# MxxxSMT.net
KiCad netlist of a schematic drawn in EAGLE
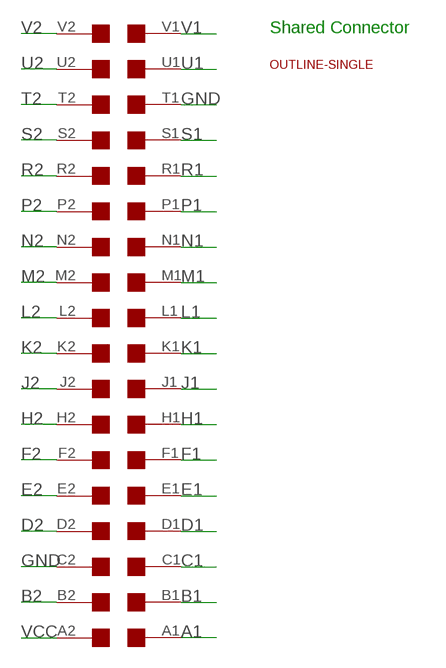
[diagram p0: schematic, sheet 1]
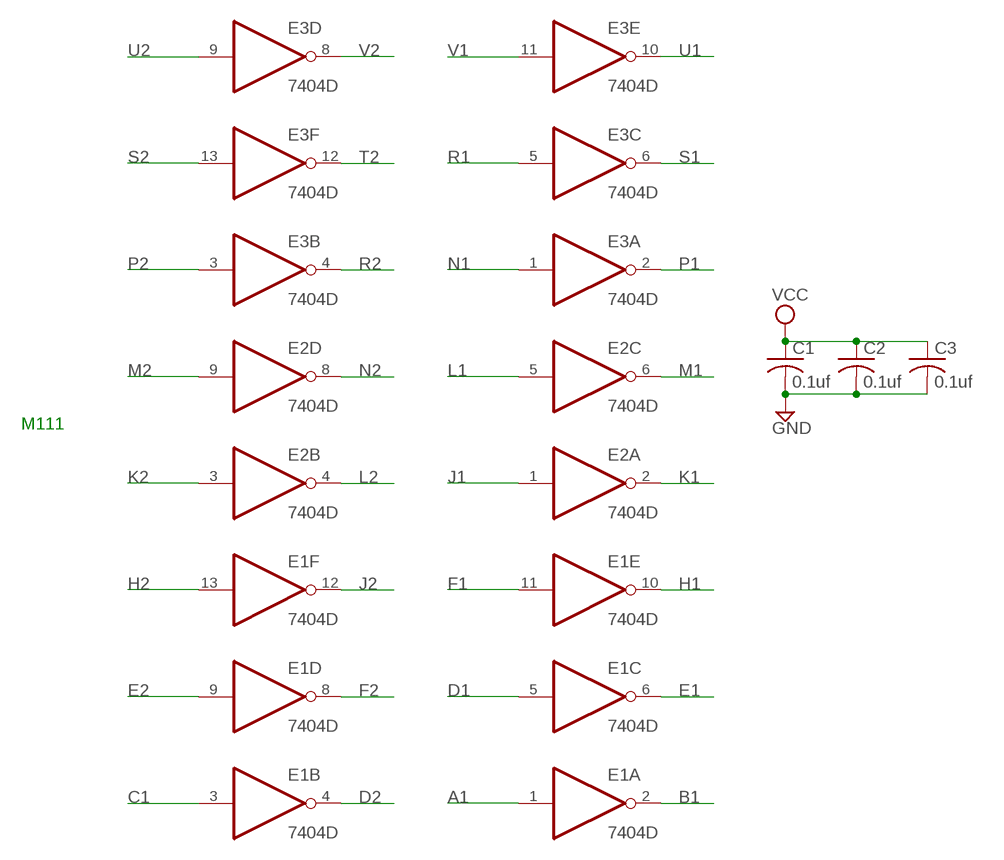
[diagram p1: schematic, sheet 2]
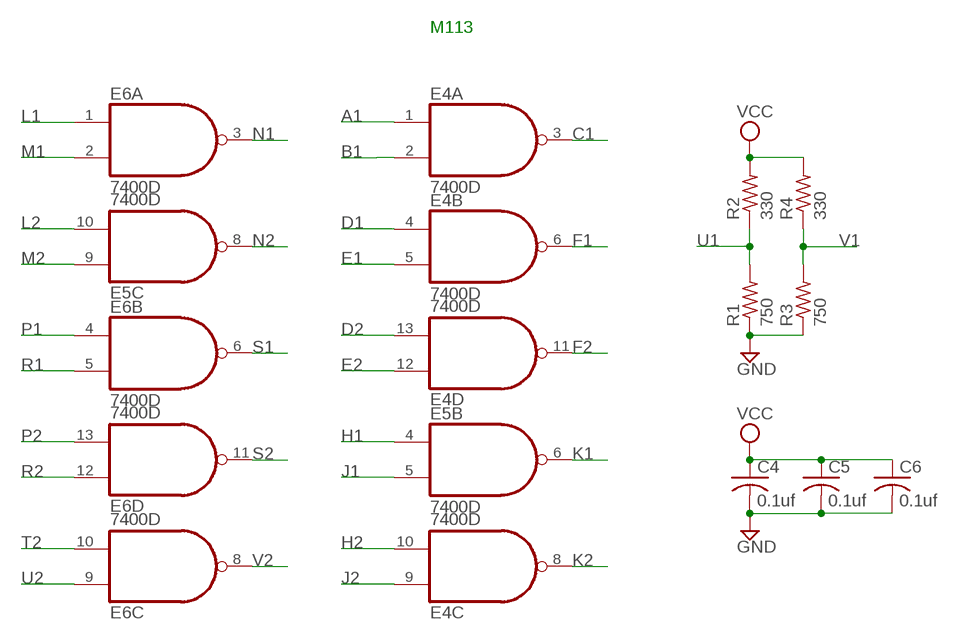
[diagram p2: schematic, sheet 3]
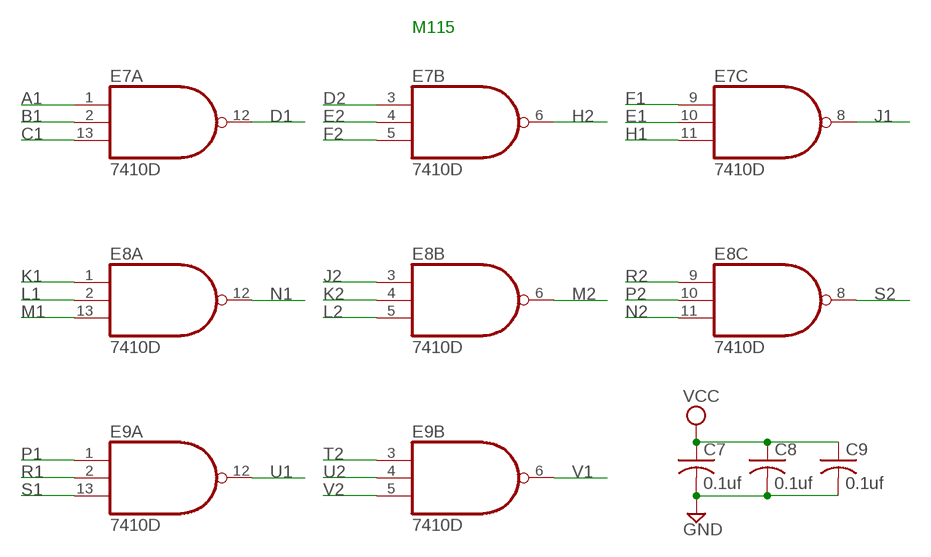
[diagram p3: schematic, sheet 4]
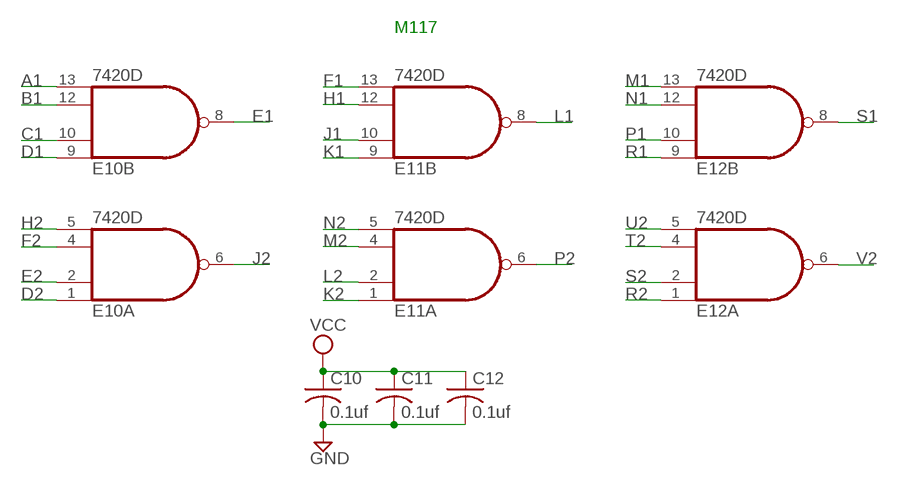
[diagram p4: schematic, sheet 5]
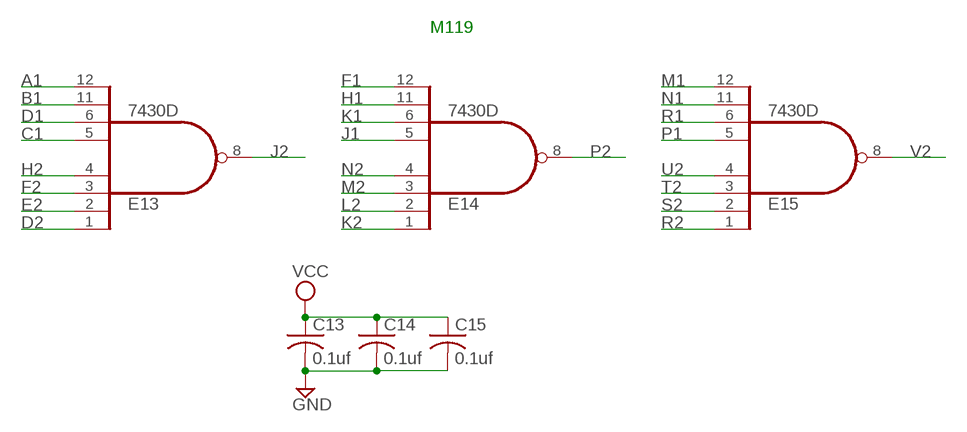
[diagram p5: schematic, sheet 6]
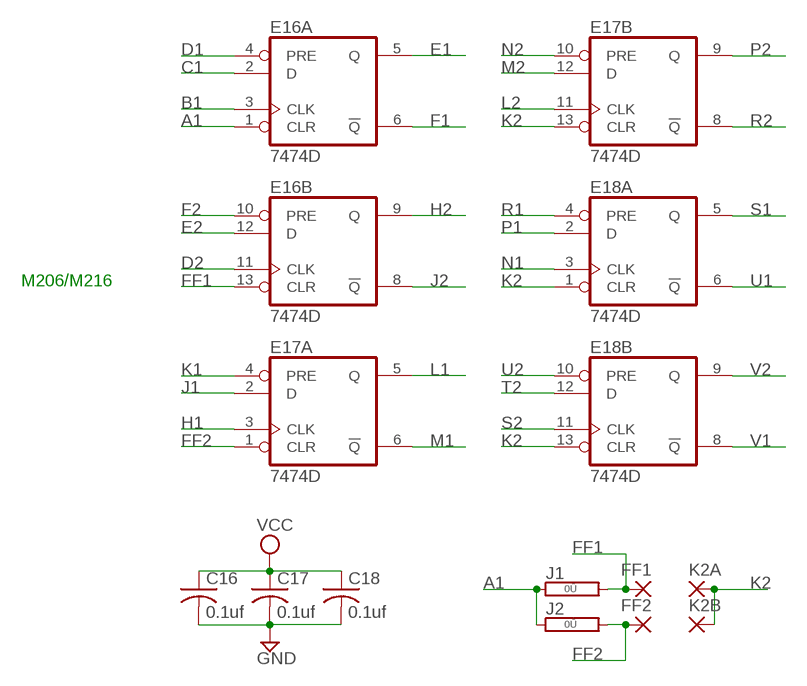
[diagram p6: schematic, sheet 7]
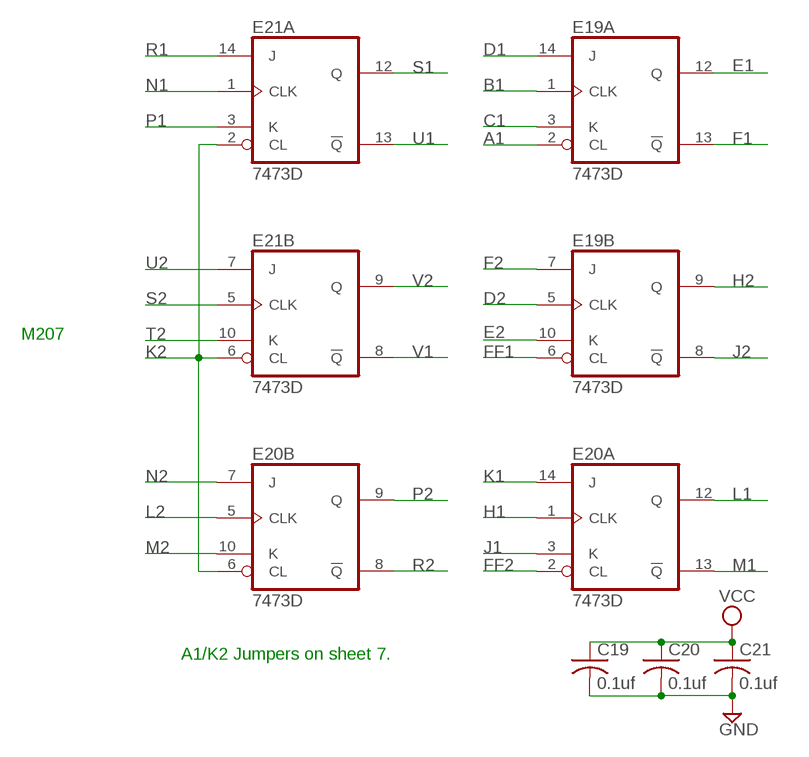
[diagram p7: schematic, sheet 8]

(export (version "E")
  (design (tool "Eeschema 10.0.6"))
  (components
    (comp (ref "C4")
      (value "0.1uf")
      (footprint "eagle-import:C050-025X075")
      (libsource (lib "eagle-import") (part "C-US050-025X075"))
    )
    (comp (ref "C5")
      (value "0.1uf")
      (footprint "eagle-import:C050-025X075")
      (libsource (lib "eagle-import") (part "C-US050-025X075"))
    )
    (comp (ref "C6")
      (value "0.1uf")
      (footprint "eagle-import:C050-025X075")
      (libsource (lib "eagle-import") (part "C-US050-025X075"))
    )
    (comp (ref "E4")
      (value "7400D")
      (footprint "eagle-import:SO14")
      (libsource (lib "eagle-import") (part "7400D"))
    )
    (comp (ref "E5")
      (value "7400D")
      (footprint "eagle-import:SO14")
      (libsource (lib "eagle-import") (part "7400D"))
    )
    (comp (ref "E6")
      (value "7400D")
      (footprint "eagle-import:SO14")
      (libsource (lib "eagle-import") (part "7400D"))
    )
    (comp (ref "R1")
      (value "750")
      (footprint "eagle-import:0207_10")
      (libsource (lib "eagle-import") (part "R-US_0207/10"))
    )
    (comp (ref "R2")
      (value "330")
      (footprint "eagle-import:0207_10")
      (libsource (lib "eagle-import") (part "R-US_0207/10"))
    )
    (comp (ref "R3")
      (value "750")
      (footprint "eagle-import:0207_10")
      (libsource (lib "eagle-import") (part "R-US_0207/10"))
    )
    (comp (ref "R4")
      (value "330")
      (footprint "eagle-import:0207_10")
      (libsource (lib "eagle-import") (part "R-US_0207/10"))
    )
    (comp (ref "C16")
      (value "0.1uf")
      (footprint "eagle-import:C050-025X075")
      (libsource (lib "eagle-import") (part "C-US050-025X075"))
    )
    (comp (ref "C17")
      (value "0.1uf")
      (footprint "eagle-import:C050-025X075")
      (libsource (lib "eagle-import") (part "C-US050-025X075"))
    )
    (comp (ref "C18")
      (value "0.1uf")
      (footprint "eagle-import:C050-025X075")
      (libsource (lib "eagle-import") (part "C-US050-025X075"))
    )
    (comp (ref "E16")
      (value "7474D")
      (footprint "eagle-import:SO14")
      (libsource (lib "eagle-import") (part "7474DS"))
    )
    (comp (ref "E17")
      (value "7474D")
      (footprint "eagle-import:SO14")
      (libsource (lib "eagle-import") (part "7474DS"))
    )
    (comp (ref "E18")
      (value "7474D")
      (footprint "eagle-import:SO14")
      (libsource (lib "eagle-import") (part "7474DS"))
    )
    (comp (ref "FF1")
      (value "1,6/0,8")
      (footprint "eagle-import:1,6_0,8")
      (libsource (lib "eagle-import") (part "1,6/0,8"))
    )
    (comp (ref "FF2")
      (value "1,6/0,8")
      (footprint "eagle-import:1,6_0,8")
      (libsource (lib "eagle-import") (part "1,6/0,8"))
    )
    (comp (ref "J1")
      (value "0R")
      (footprint "eagle-import:0R_10")
      (libsource (lib "eagle-import") (part "0R"))
    )
    (comp (ref "J2")
      (value "0R")
      (footprint "eagle-import:0R_10")
      (libsource (lib "eagle-import") (part "0R"))
    )
    (comp (ref "K2A")
      (value "1,6/0,8")
      (footprint "eagle-import:1,6_0,8")
      (libsource (lib "eagle-import") (part "1,6/0,8"))
    )
    (comp (ref "K2B")
      (value "1,6/0,8")
      (footprint "eagle-import:1,6_0,8")
      (libsource (lib "eagle-import") (part "1,6/0,8"))
    )
    (comp (ref "C13")
      (value "0.1uf")
      (footprint "eagle-import:C050-025X075")
      (libsource (lib "eagle-import") (part "C-US050-025X075"))
    )
    (comp (ref "C14")
      (value "0.1uf")
      (footprint "eagle-import:C050-025X075")
      (libsource (lib "eagle-import") (part "C-US050-025X075"))
    )
    (comp (ref "C15")
      (value "0.1uf")
      (footprint "eagle-import:C050-025X075")
      (libsource (lib "eagle-import") (part "C-US050-025X075"))
    )
    (comp (ref "E13")
      (value "7430D")
      (footprint "eagle-import:SO14")
      (libsource (lib "eagle-import") (part "7430D"))
    )
    (comp (ref "E14")
      (value "7430D")
      (footprint "eagle-import:SO14")
      (libsource (lib "eagle-import") (part "7430D"))
    )
    (comp (ref "E15")
      (value "7430D")
      (footprint "eagle-import:SO14")
      (libsource (lib "eagle-import") (part "7430D"))
    )
    (comp (ref "C19")
      (value "0.1uf")
      (footprint "eagle-import:C050-025X075")
      (libsource (lib "eagle-import") (part "C-US050-025X075"))
    )
    (comp (ref "C20")
      (value "0.1uf")
      (footprint "eagle-import:C050-025X075")
      (libsource (lib "eagle-import") (part "C-US050-025X075"))
    )
    (comp (ref "C21")
      (value "0.1uf")
      (footprint "eagle-import:C050-025X075")
      (libsource (lib "eagle-import") (part "C-US050-025X075"))
    )
    (comp (ref "E19")
      (value "7473D")
      (footprint "eagle-import:SO14")
      (libsource (lib "eagle-import") (part "7473DLS"))
    )
    (comp (ref "E20")
      (value "7473D")
      (footprint "eagle-import:SO14")
      (libsource (lib "eagle-import") (part "7473DLS"))
    )
    (comp (ref "E21")
      (value "7473D")
      (footprint "eagle-import:SO14")
      (libsource (lib "eagle-import") (part "7473DLS"))
    )
    (comp (ref "C7")
      (value "0.1uf")
      (footprint "eagle-import:C050-025X075")
      (libsource (lib "eagle-import") (part "C-US050-025X075"))
    )
    (comp (ref "C8")
      (value "0.1uf")
      (footprint "eagle-import:C050-025X075")
      (libsource (lib "eagle-import") (part "C-US050-025X075"))
    )
    (comp (ref "C9")
      (value "0.1uf")
      (footprint "eagle-import:C050-025X075")
      (libsource (lib "eagle-import") (part "C-US050-025X075"))
    )
    (comp (ref "E7")
      (value "7410D")
      (footprint "eagle-import:SO14")
      (libsource (lib "eagle-import") (part "7410D"))
    )
    (comp (ref "E8")
      (value "7410D")
      (footprint "eagle-import:SO14")
      (libsource (lib "eagle-import") (part "7410D"))
    )
    (comp (ref "E9")
      (value "7410D")
      (footprint "eagle-import:SO14")
      (libsource (lib "eagle-import") (part "7410D"))
    )
    (comp (ref "C1")
      (value "0.1uf")
      (footprint "eagle-import:C050-025X075")
      (libsource (lib "eagle-import") (part "C-US050-025X075"))
    )
    (comp (ref "C2")
      (value "0.1uf")
      (footprint "eagle-import:C050-025X075")
      (libsource (lib "eagle-import") (part "C-US050-025X075"))
    )
    (comp (ref "C3")
      (value "0.1uf")
      (footprint "eagle-import:C050-025X075")
      (libsource (lib "eagle-import") (part "C-US050-025X075"))
    )
    (comp (ref "E1")
      (value "7404D")
      (footprint "eagle-import:SO14")
      (libsource (lib "eagle-import") (part "7404D"))
    )
    (comp (ref "E2")
      (value "7404D")
      (footprint "eagle-import:SO14")
      (libsource (lib "eagle-import") (part "7404D"))
    )
    (comp (ref "E3")
      (value "7404D")
      (footprint "eagle-import:SO14")
      (libsource (lib "eagle-import") (part "7404D"))
    )
    (comp (ref "C10")
      (value "0.1uf")
      (footprint "eagle-import:C050-025X075")
      (libsource (lib "eagle-import") (part "C-US050-025X075"))
    )
    (comp (ref "C11")
      (value "0.1uf")
      (footprint "eagle-import:C050-025X075")
      (libsource (lib "eagle-import") (part "C-US050-025X075"))
    )
    (comp (ref "C12")
      (value "0.1uf")
      (footprint "eagle-import:C050-025X075")
      (libsource (lib "eagle-import") (part "C-US050-025X075"))
    )
    (comp (ref "E10")
      (value "7420D")
      (footprint "eagle-import:SO14")
      (libsource (lib "eagle-import") (part "7420DS"))
    )
    (comp (ref "E11")
      (value "7420D")
      (footprint "eagle-import:SO14")
      (libsource (lib "eagle-import") (part "7420DS"))
    )
    (comp (ref "E12")
      (value "7420D")
      (footprint "eagle-import:SO14")
      (libsource (lib "eagle-import") (part "7420DS"))
    )
    (comp (ref "U$1")
      (value "EDGE-2CONNECTOR")
      (footprint "eagle-import:EDGE-CON2")
      (libsource (lib "eagle-import") (part "EDGE-2CONNECTOR"))
    )
    (comp (ref "U$4")
      (value "OUTLINE-SINGLE")
      (footprint "eagle-import:SINGLE")
      (libsource (lib "eagle-import") (part "OUTLINE-SINGLE"))
    )
  )
  (nets
    (net (code "1") (name "A1") (class "Default")
      (node (ref "E1") (pin "1") (pinfunction "I_1") (pintype "input"))
      (node (ref "E10") (pin "13") (pinfunction "I3_13") (pintype "input"))
      (node (ref "E13") (pin "12") (pinfunction "I7_12") (pintype "input"))
      (node (ref "E16") (pin "1") (pinfunction "CLR_1") (pintype "input"))
      (node (ref "E19") (pin "2") (pinfunction "CL_2") (pintype "input"))
      (node (ref "E4") (pin "1") (pinfunction "I0_1") (pintype "input"))
      (node (ref "E7") (pin "1") (pinfunction "I0_1") (pintype "input"))
      (node (ref "J1") (pin "1") (pinfunction "1_1") (pintype "passive"))
      (node (ref "J2") (pin "1") (pinfunction "1_1") (pintype "passive"))
      (node (ref "U$1") (pin "A1") (pinfunction "1_A1") (pintype "bidirectional"))
    )
    (net (code "2") (name "B1") (class "Default")
      (node (ref "E1") (pin "2") (pinfunction "O_2") (pintype "output"))
      (node (ref "E10") (pin "12") (pinfunction "I2_12") (pintype "input"))
      (node (ref "E13") (pin "11") (pinfunction "I6_11") (pintype "input"))
      (node (ref "E16") (pin "3") (pinfunction "CLK_3") (pintype "input"))
      (node (ref "E19") (pin "1") (pinfunction "CLK_1") (pintype "input"))
      (node (ref "E4") (pin "2") (pinfunction "I1_2") (pintype "input"))
      (node (ref "E7") (pin "2") (pinfunction "I1_2") (pintype "input"))
      (node (ref "U$1") (pin "B1") (pinfunction "1_B1") (pintype "bidirectional"))
    )
    (net (code "3") (name "B2") (class "Default")
      (node (ref "U$1") (pin "B2") (pinfunction "1_B2") (pintype "bidirectional"))
    )
    (net (code "4") (name "C1") (class "Default")
      (node (ref "E1") (pin "3") (pinfunction "I_3") (pintype "input"))
      (node (ref "E10") (pin "10") (pinfunction "I1_10") (pintype "input"))
      (node (ref "E13") (pin "5") (pinfunction "I4_5") (pintype "input"))
      (node (ref "E16") (pin "2") (pinfunction "D_2") (pintype "input"))
      (node (ref "E19") (pin "3") (pinfunction "K_3") (pintype "input"))
      (node (ref "E4") (pin "3") (pinfunction "O_3") (pintype "output"))
      (node (ref "E7") (pin "13") (pinfunction "I2_13") (pintype "input"))
      (node (ref "U$1") (pin "C1") (pinfunction "1_C1") (pintype "bidirectional"))
    )
    (net (code "5") (name "D1") (class "Default")
      (node (ref "E1") (pin "5") (pinfunction "I_5") (pintype "input"))
      (node (ref "E10") (pin "9") (pinfunction "I0_9") (pintype "input"))
      (node (ref "E13") (pin "6") (pinfunction "I5_6") (pintype "input"))
      (node (ref "E16") (pin "4") (pinfunction "PRE_4") (pintype "input"))
      (node (ref "E19") (pin "14") (pinfunction "J_14") (pintype "input"))
      (node (ref "E4") (pin "4") (pinfunction "I0_4") (pintype "input"))
      (node (ref "E7") (pin "12") (pinfunction "O_12") (pintype "output"))
      (node (ref "U$1") (pin "D1") (pinfunction "1_D1") (pintype "bidirectional"))
    )
    (net (code "6") (name "D2") (class "Default")
      (node (ref "E1") (pin "4") (pinfunction "O_4") (pintype "output"))
      (node (ref "E10") (pin "1") (pinfunction "I0_1") (pintype "input"))
      (node (ref "E13") (pin "1") (pinfunction "I0_1") (pintype "input"))
      (node (ref "E16") (pin "11") (pinfunction "CLK_11") (pintype "input"))
      (node (ref "E19") (pin "5") (pinfunction "CLK_5") (pintype "input"))
      (node (ref "E4") (pin "13") (pinfunction "I1_13") (pintype "input"))
      (node (ref "E7") (pin "3") (pinfunction "I0_3") (pintype "input"))
      (node (ref "U$1") (pin "D2") (pinfunction "1_D2") (pintype "bidirectional"))
    )
    (net (code "7") (name "E1") (class "Default")
      (node (ref "E1") (pin "6") (pinfunction "O_6") (pintype "output"))
      (node (ref "E10") (pin "8") (pinfunction "O_8") (pintype "output"))
      (node (ref "E16") (pin "5") (pinfunction "Q_5") (pintype "output"))
      (node (ref "E19") (pin "12") (pinfunction "Q_12") (pintype "output"))
      (node (ref "E4") (pin "5") (pinfunction "I1_5") (pintype "input"))
      (node (ref "E7") (pin "10") (pinfunction "I1_10") (pintype "input"))
      (node (ref "U$1") (pin "E1") (pinfunction "1_E1") (pintype "bidirectional"))
    )
    (net (code "8") (name "E2") (class "Default")
      (node (ref "E1") (pin "9") (pinfunction "I_9") (pintype "input"))
      (node (ref "E10") (pin "2") (pinfunction "I1_2") (pintype "input"))
      (node (ref "E13") (pin "2") (pinfunction "I1_2") (pintype "input"))
      (node (ref "E16") (pin "12") (pinfunction "D_12") (pintype "input"))
      (node (ref "E19") (pin "10") (pinfunction "K_10") (pintype "input"))
      (node (ref "E4") (pin "12") (pinfunction "I0_12") (pintype "input"))
      (node (ref "E7") (pin "4") (pinfunction "I1_4") (pintype "input"))
      (node (ref "U$1") (pin "E2") (pinfunction "1_E2") (pintype "bidirectional"))
    )
    (net (code "9") (name "F1") (class "Default")
      (node (ref "E1") (pin "11") (pinfunction "I_11") (pintype "input"))
      (node (ref "E11") (pin "13") (pinfunction "I3_13") (pintype "input"))
      (node (ref "E14") (pin "12") (pinfunction "I7_12") (pintype "input"))
      (node (ref "E16") (pin "6") (pinfunction "~{Q}_6") (pintype "output"))
      (node (ref "E19") (pin "13") (pinfunction "~{Q}_13") (pintype "output"))
      (node (ref "E4") (pin "6") (pinfunction "O_6") (pintype "output"))
      (node (ref "E7") (pin "9") (pinfunction "I0_9") (pintype "input"))
      (node (ref "U$1") (pin "F1") (pinfunction "1_F1") (pintype "bidirectional"))
    )
    (net (code "10") (name "F2") (class "Default")
      (node (ref "E1") (pin "8") (pinfunction "O_8") (pintype "output"))
      (node (ref "E10") (pin "4") (pinfunction "I2_4") (pintype "input"))
      (node (ref "E13") (pin "3") (pinfunction "I2_3") (pintype "input"))
      (node (ref "E16") (pin "10") (pinfunction "PRE_10") (pintype "input"))
      (node (ref "E19") (pin "7") (pinfunction "J_7") (pintype "input"))
      (node (ref "E4") (pin "11") (pinfunction "O_11") (pintype "output"))
      (node (ref "E7") (pin "5") (pinfunction "I2_5") (pintype "input"))
      (node (ref "U$1") (pin "F2") (pinfunction "1_F2") (pintype "bidirectional"))
    )
    (net (code "11") (name "FF1") (class "Default")
      (node (ref "E16") (pin "13") (pinfunction "CLR_13") (pintype "input"))
      (node (ref "E19") (pin "6") (pinfunction "CL_6") (pintype "input"))
      (node (ref "FF1") (pin "1") (pinfunction "P_1") (pintype "passive"))
      (node (ref "J1") (pin "2") (pinfunction "2_2") (pintype "passive"))
    )
    (net (code "12") (name "FF2") (class "Default")
      (node (ref "E17") (pin "1") (pinfunction "CLR_1") (pintype "input"))
      (node (ref "E20") (pin "2") (pinfunction "CL_2") (pintype "input"))
      (node (ref "FF2") (pin "1") (pinfunction "P_1") (pintype "passive"))
      (node (ref "J2") (pin "2") (pinfunction "2_2") (pintype "passive"))
    )
    (net (code "13") (name "GND") (class "Default")
      (node (ref "C1") (pin "2") (pinfunction "2_2") (pintype "passive"))
      (node (ref "C10") (pin "2") (pinfunction "2_2") (pintype "passive"))
      (node (ref "C11") (pin "2") (pinfunction "2_2") (pintype "passive"))
      (node (ref "C12") (pin "2") (pinfunction "2_2") (pintype "passive"))
      (node (ref "C13") (pin "2") (pinfunction "2_2") (pintype "passive"))
      (node (ref "C14") (pin "2") (pinfunction "2_2") (pintype "passive"))
      (node (ref "C15") (pin "2") (pinfunction "2_2") (pintype "passive"))
      (node (ref "C16") (pin "2") (pinfunction "2_2") (pintype "passive"))
      (node (ref "C17") (pin "2") (pinfunction "2_2") (pintype "passive"))
      (node (ref "C18") (pin "2") (pinfunction "2_2") (pintype "passive"))
      (node (ref "C19") (pin "2") (pinfunction "2_2") (pintype "passive"))
      (node (ref "C2") (pin "2") (pinfunction "2_2") (pintype "passive"))
      (node (ref "C20") (pin "2") (pinfunction "2_2") (pintype "passive"))
      (node (ref "C21") (pin "2") (pinfunction "2_2") (pintype "passive"))
      (node (ref "C3") (pin "2") (pinfunction "2_2") (pintype "passive"))
      (node (ref "C4") (pin "2") (pinfunction "2_2") (pintype "passive"))
      (node (ref "C5") (pin "2") (pinfunction "2_2") (pintype "passive"))
      (node (ref "C6") (pin "2") (pinfunction "2_2") (pintype "passive"))
      (node (ref "C7") (pin "2") (pinfunction "2_2") (pintype "passive"))
      (node (ref "C8") (pin "2") (pinfunction "2_2") (pintype "passive"))
      (node (ref "C9") (pin "2") (pinfunction "2_2") (pintype "passive"))
      (node (ref "R1") (pin "1") (pinfunction "1_1") (pintype "passive"))
      (node (ref "R3") (pin "1") (pinfunction "1_1") (pintype "passive"))
      (node (ref "U$1") (pin "C2") (pinfunction "1_C2") (pintype "bidirectional"))
      (node (ref "U$1") (pin "T1") (pinfunction "1_T1") (pintype "bidirectional"))
    )
    (net (code "14") (name "H1") (class "Default")
      (node (ref "E1") (pin "10") (pinfunction "O_10") (pintype "output"))
      (node (ref "E11") (pin "12") (pinfunction "I2_12") (pintype "input"))
      (node (ref "E14") (pin "11") (pinfunction "I6_11") (pintype "input"))
      (node (ref "E17") (pin "3") (pinfunction "CLK_3") (pintype "input"))
      (node (ref "E20") (pin "1") (pinfunction "CLK_1") (pintype "input"))
      (node (ref "E5") (pin "4") (pinfunction "I0_4") (pintype "input"))
      (node (ref "E7") (pin "11") (pinfunction "I2_11") (pintype "input"))
      (node (ref "U$1") (pin "H1") (pinfunction "1_H1") (pintype "bidirectional"))
    )
    (net (code "15") (name "H2") (class "Default")
      (node (ref "E1") (pin "13") (pinfunction "I_13") (pintype "input"))
      (node (ref "E10") (pin "5") (pinfunction "I3_5") (pintype "input"))
      (node (ref "E13") (pin "4") (pinfunction "I3_4") (pintype "input"))
      (node (ref "E16") (pin "9") (pinfunction "Q_9") (pintype "output"))
      (node (ref "E19") (pin "9") (pinfunction "Q_9") (pintype "output"))
      (node (ref "E4") (pin "10") (pinfunction "I1_10") (pintype "input"))
      (node (ref "E7") (pin "6") (pinfunction "O_6") (pintype "output"))
      (node (ref "U$1") (pin "H2") (pinfunction "1_H2") (pintype "bidirectional"))
    )
    (net (code "16") (name "J1") (class "Default")
      (node (ref "E11") (pin "10") (pinfunction "I1_10") (pintype "input"))
      (node (ref "E14") (pin "5") (pinfunction "I4_5") (pintype "input"))
      (node (ref "E17") (pin "2") (pinfunction "D_2") (pintype "input"))
      (node (ref "E2") (pin "1") (pinfunction "I_1") (pintype "input"))
      (node (ref "E20") (pin "3") (pinfunction "K_3") (pintype "input"))
      (node (ref "E5") (pin "5") (pinfunction "I1_5") (pintype "input"))
      (node (ref "E7") (pin "8") (pinfunction "O_8") (pintype "output"))
      (node (ref "U$1") (pin "J1") (pinfunction "1_J1") (pintype "bidirectional"))
    )
    (net (code "17") (name "J2") (class "Default")
      (node (ref "E1") (pin "12") (pinfunction "O_12") (pintype "output"))
      (node (ref "E10") (pin "6") (pinfunction "O_6") (pintype "output"))
      (node (ref "E13") (pin "8") (pinfunction "O_8") (pintype "output"))
      (node (ref "E16") (pin "8") (pinfunction "~{Q}_8") (pintype "output"))
      (node (ref "E19") (pin "8") (pinfunction "~{Q}_8") (pintype "output"))
      (node (ref "E4") (pin "9") (pinfunction "I0_9") (pintype "input"))
      (node (ref "E8") (pin "3") (pinfunction "I0_3") (pintype "input"))
      (node (ref "U$1") (pin "J2") (pinfunction "1_J2") (pintype "bidirectional"))
    )
    (net (code "18") (name "K1") (class "Default")
      (node (ref "E11") (pin "9") (pinfunction "I0_9") (pintype "input"))
      (node (ref "E14") (pin "6") (pinfunction "I5_6") (pintype "input"))
      (node (ref "E17") (pin "4") (pinfunction "PRE_4") (pintype "input"))
      (node (ref "E2") (pin "2") (pinfunction "O_2") (pintype "output"))
      (node (ref "E20") (pin "14") (pinfunction "J_14") (pintype "input"))
      (node (ref "E5") (pin "6") (pinfunction "O_6") (pintype "output"))
      (node (ref "E8") (pin "1") (pinfunction "I0_1") (pintype "input"))
      (node (ref "U$1") (pin "K1") (pinfunction "1_K1") (pintype "bidirectional"))
    )
    (net (code "19") (name "K2") (class "Default")
      (node (ref "E11") (pin "1") (pinfunction "I0_1") (pintype "input"))
      (node (ref "E14") (pin "1") (pinfunction "I0_1") (pintype "input"))
      (node (ref "E17") (pin "13") (pinfunction "CLR_13") (pintype "input"))
      (node (ref "E18") (pin "1") (pinfunction "CLR_1") (pintype "input"))
      (node (ref "E18") (pin "13") (pinfunction "CLR_13") (pintype "input"))
      (node (ref "E2") (pin "3") (pinfunction "I_3") (pintype "input"))
      (node (ref "E20") (pin "6") (pinfunction "CL_6") (pintype "input"))
      (node (ref "E21") (pin "2") (pinfunction "CL_2") (pintype "input"))
      (node (ref "E21") (pin "6") (pinfunction "CL_6") (pintype "input"))
      (node (ref "E4") (pin "8") (pinfunction "O_8") (pintype "output"))
      (node (ref "E8") (pin "4") (pinfunction "I1_4") (pintype "input"))
      (node (ref "K2A") (pin "1") (pinfunction "P_1") (pintype "passive"))
      (node (ref "K2B") (pin "1") (pinfunction "P_1") (pintype "passive"))
      (node (ref "U$1") (pin "K2") (pinfunction "1_K2") (pintype "bidirectional"))
    )
    (net (code "20") (name "L1") (class "Default")
      (node (ref "E11") (pin "8") (pinfunction "O_8") (pintype "output"))
      (node (ref "E17") (pin "5") (pinfunction "Q_5") (pintype "output"))
      (node (ref "E2") (pin "5") (pinfunction "I_5") (pintype "input"))
      (node (ref "E20") (pin "12") (pinfunction "Q_12") (pintype "output"))
      (node (ref "E6") (pin "1") (pinfunction "I0_1") (pintype "input"))
      (node (ref "E8") (pin "2") (pinfunction "I1_2") (pintype "input"))
      (node (ref "U$1") (pin "L1") (pinfunction "1_L1") (pintype "bidirectional"))
    )
    (net (code "21") (name "L2") (class "Default")
      (node (ref "E11") (pin "2") (pinfunction "I1_2") (pintype "input"))
      (node (ref "E14") (pin "2") (pinfunction "I1_2") (pintype "input"))
      (node (ref "E17") (pin "11") (pinfunction "CLK_11") (pintype "input"))
      (node (ref "E2") (pin "4") (pinfunction "O_4") (pintype "output"))
      (node (ref "E20") (pin "5") (pinfunction "CLK_5") (pintype "input"))
      (node (ref "E5") (pin "10") (pinfunction "I1_10") (pintype "input"))
      (node (ref "E8") (pin "5") (pinfunction "I2_5") (pintype "input"))
      (node (ref "U$1") (pin "L2") (pinfunction "1_L2") (pintype "bidirectional"))
    )
    (net (code "22") (name "M1") (class "Default")
      (node (ref "E12") (pin "13") (pinfunction "I3_13") (pintype "input"))
      (node (ref "E15") (pin "12") (pinfunction "I7_12") (pintype "input"))
      (node (ref "E17") (pin "6") (pinfunction "~{Q}_6") (pintype "output"))
      (node (ref "E2") (pin "6") (pinfunction "O_6") (pintype "output"))
      (node (ref "E20") (pin "13") (pinfunction "~{Q}_13") (pintype "output"))
      (node (ref "E6") (pin "2") (pinfunction "I1_2") (pintype "input"))
      (node (ref "E8") (pin "13") (pinfunction "I2_13") (pintype "input"))
      (node (ref "U$1") (pin "M1") (pinfunction "1_M1") (pintype "bidirectional"))
    )
    (net (code "23") (name "M2") (class "Default")
      (node (ref "E11") (pin "4") (pinfunction "I2_4") (pintype "input"))
      (node (ref "E14") (pin "3") (pinfunction "I2_3") (pintype "input"))
      (node (ref "E17") (pin "12") (pinfunction "D_12") (pintype "input"))
      (node (ref "E2") (pin "9") (pinfunction "I_9") (pintype "input"))
      (node (ref "E20") (pin "10") (pinfunction "K_10") (pintype "input"))
      (node (ref "E5") (pin "9") (pinfunction "I0_9") (pintype "input"))
      (node (ref "E8") (pin "6") (pinfunction "O_6") (pintype "output"))
      (node (ref "U$1") (pin "M2") (pinfunction "1_M2") (pintype "bidirectional"))
    )
    (net (code "24") (name "N1") (class "Default")
      (node (ref "E12") (pin "12") (pinfunction "I2_12") (pintype "input"))
      (node (ref "E15") (pin "11") (pinfunction "I6_11") (pintype "input"))
      (node (ref "E18") (pin "3") (pinfunction "CLK_3") (pintype "input"))
      (node (ref "E21") (pin "1") (pinfunction "CLK_1") (pintype "input"))
      (node (ref "E3") (pin "1") (pinfunction "I_1") (pintype "input"))
      (node (ref "E6") (pin "3") (pinfunction "O_3") (pintype "output"))
      (node (ref "E8") (pin "12") (pinfunction "O_12") (pintype "output"))
      (node (ref "U$1") (pin "N1") (pinfunction "1_N1") (pintype "bidirectional"))
    )
    (net (code "25") (name "N2") (class "Default")
      (node (ref "E11") (pin "5") (pinfunction "I3_5") (pintype "input"))
      (node (ref "E14") (pin "4") (pinfunction "I3_4") (pintype "input"))
      (node (ref "E17") (pin "10") (pinfunction "PRE_10") (pintype "input"))
      (node (ref "E2") (pin "8") (pinfunction "O_8") (pintype "output"))
      (node (ref "E20") (pin "7") (pinfunction "J_7") (pintype "input"))
      (node (ref "E5") (pin "8") (pinfunction "O_8") (pintype "output"))
      (node (ref "E8") (pin "11") (pinfunction "I2_11") (pintype "input"))
      (node (ref "U$1") (pin "N2") (pinfunction "1_N2") (pintype "bidirectional"))
    )
    (net (code "26") (name "P1") (class "Default")
      (node (ref "E12") (pin "10") (pinfunction "I1_10") (pintype "input"))
      (node (ref "E15") (pin "5") (pinfunction "I4_5") (pintype "input"))
      (node (ref "E18") (pin "2") (pinfunction "D_2") (pintype "input"))
      (node (ref "E21") (pin "3") (pinfunction "K_3") (pintype "input"))
      (node (ref "E3") (pin "2") (pinfunction "O_2") (pintype "output"))
      (node (ref "E6") (pin "4") (pinfunction "I0_4") (pintype "input"))
      (node (ref "E9") (pin "1") (pinfunction "I0_1") (pintype "input"))
      (node (ref "U$1") (pin "P1") (pinfunction "1_P1") (pintype "bidirectional"))
    )
    (net (code "27") (name "P2") (class "Default")
      (node (ref "E11") (pin "6") (pinfunction "O_6") (pintype "output"))
      (node (ref "E14") (pin "8") (pinfunction "O_8") (pintype "output"))
      (node (ref "E17") (pin "9") (pinfunction "Q_9") (pintype "output"))
      (node (ref "E20") (pin "9") (pinfunction "Q_9") (pintype "output"))
      (node (ref "E3") (pin "3") (pinfunction "I_3") (pintype "input"))
      (node (ref "E6") (pin "13") (pinfunction "I1_13") (pintype "input"))
      (node (ref "E8") (pin "10") (pinfunction "I1_10") (pintype "input"))
      (node (ref "U$1") (pin "P2") (pinfunction "1_P2") (pintype "bidirectional"))
    )
    (net (code "28") (name "R1") (class "Default")
      (node (ref "E12") (pin "9") (pinfunction "I0_9") (pintype "input"))
      (node (ref "E15") (pin "6") (pinfunction "I5_6") (pintype "input"))
      (node (ref "E18") (pin "4") (pinfunction "PRE_4") (pintype "input"))
      (node (ref "E21") (pin "14") (pinfunction "J_14") (pintype "input"))
      (node (ref "E3") (pin "5") (pinfunction "I_5") (pintype "input"))
      (node (ref "E6") (pin "5") (pinfunction "I1_5") (pintype "input"))
      (node (ref "E9") (pin "2") (pinfunction "I1_2") (pintype "input"))
      (node (ref "U$1") (pin "R1") (pinfunction "1_R1") (pintype "bidirectional"))
    )
    (net (code "29") (name "R2") (class "Default")
      (node (ref "E12") (pin "1") (pinfunction "I0_1") (pintype "input"))
      (node (ref "E15") (pin "1") (pinfunction "I0_1") (pintype "input"))
      (node (ref "E17") (pin "8") (pinfunction "~{Q}_8") (pintype "output"))
      (node (ref "E20") (pin "8") (pinfunction "~{Q}_8") (pintype "output"))
      (node (ref "E3") (pin "4") (pinfunction "O_4") (pintype "output"))
      (node (ref "E6") (pin "12") (pinfunction "I0_12") (pintype "input"))
      (node (ref "E8") (pin "9") (pinfunction "I0_9") (pintype "input"))
      (node (ref "U$1") (pin "R2") (pinfunction "1_R2") (pintype "bidirectional"))
    )
    (net (code "30") (name "S1") (class "Default")
      (node (ref "E12") (pin "8") (pinfunction "O_8") (pintype "output"))
      (node (ref "E18") (pin "5") (pinfunction "Q_5") (pintype "output"))
      (node (ref "E21") (pin "12") (pinfunction "Q_12") (pintype "output"))
      (node (ref "E3") (pin "6") (pinfunction "O_6") (pintype "output"))
      (node (ref "E6") (pin "6") (pinfunction "O_6") (pintype "output"))
      (node (ref "E9") (pin "13") (pinfunction "I2_13") (pintype "input"))
      (node (ref "U$1") (pin "S1") (pinfunction "1_S1") (pintype "bidirectional"))
    )
    (net (code "31") (name "S2") (class "Default")
      (node (ref "E12") (pin "2") (pinfunction "I1_2") (pintype "input"))
      (node (ref "E15") (pin "2") (pinfunction "I1_2") (pintype "input"))
      (node (ref "E18") (pin "11") (pinfunction "CLK_11") (pintype "input"))
      (node (ref "E21") (pin "5") (pinfunction "CLK_5") (pintype "input"))
      (node (ref "E3") (pin "13") (pinfunction "I_13") (pintype "input"))
      (node (ref "E6") (pin "11") (pinfunction "O_11") (pintype "output"))
      (node (ref "E8") (pin "8") (pinfunction "O_8") (pintype "output"))
      (node (ref "U$1") (pin "S2") (pinfunction "1_S2") (pintype "bidirectional"))
    )
    (net (code "32") (name "T2") (class "Default")
      (node (ref "E12") (pin "4") (pinfunction "I2_4") (pintype "input"))
      (node (ref "E15") (pin "3") (pinfunction "I2_3") (pintype "input"))
      (node (ref "E18") (pin "12") (pinfunction "D_12") (pintype "input"))
      (node (ref "E21") (pin "10") (pinfunction "K_10") (pintype "input"))
      (node (ref "E3") (pin "12") (pinfunction "O_12") (pintype "output"))
      (node (ref "E6") (pin "10") (pinfunction "I1_10") (pintype "input"))
      (node (ref "E9") (pin "3") (pinfunction "I0_3") (pintype "input"))
      (node (ref "U$1") (pin "T2") (pinfunction "1_T2") (pintype "bidirectional"))
    )
    (net (code "33") (name "U1") (class "Default")
      (node (ref "E18") (pin "6") (pinfunction "~{Q}_6") (pintype "output"))
      (node (ref "E21") (pin "13") (pinfunction "~{Q}_13") (pintype "output"))
      (node (ref "E3") (pin "10") (pinfunction "O_10") (pintype "output"))
      (node (ref "E9") (pin "12") (pinfunction "O_12") (pintype "output"))
      (node (ref "R1") (pin "2") (pinfunction "2_2") (pintype "passive"))
      (node (ref "R2") (pin "1") (pinfunction "1_1") (pintype "passive"))
      (node (ref "U$1") (pin "U1") (pinfunction "1_U1") (pintype "bidirectional"))
    )
    (net (code "34") (name "U2") (class "Default")
      (node (ref "E12") (pin "5") (pinfunction "I3_5") (pintype "input"))
      (node (ref "E15") (pin "4") (pinfunction "I3_4") (pintype "input"))
      (node (ref "E18") (pin "10") (pinfunction "PRE_10") (pintype "input"))
      (node (ref "E21") (pin "7") (pinfunction "J_7") (pintype "input"))
      (node (ref "E3") (pin "9") (pinfunction "I_9") (pintype "input"))
      (node (ref "E6") (pin "9") (pinfunction "I0_9") (pintype "input"))
      (node (ref "E9") (pin "4") (pinfunction "I1_4") (pintype "input"))
      (node (ref "U$1") (pin "U2") (pinfunction "1_U2") (pintype "bidirectional"))
    )
    (net (code "35") (name "V1") (class "Default")
      (node (ref "E18") (pin "8") (pinfunction "~{Q}_8") (pintype "output"))
      (node (ref "E21") (pin "8") (pinfunction "~{Q}_8") (pintype "output"))
      (node (ref "E3") (pin "11") (pinfunction "I_11") (pintype "input"))
      (node (ref "E9") (pin "6") (pinfunction "O_6") (pintype "output"))
      (node (ref "R3") (pin "2") (pinfunction "2_2") (pintype "passive"))
      (node (ref "R4") (pin "1") (pinfunction "1_1") (pintype "passive"))
      (node (ref "U$1") (pin "V1") (pinfunction "1_V1") (pintype "bidirectional"))
    )
    (net (code "36") (name "V2") (class "Default")
      (node (ref "E12") (pin "6") (pinfunction "O_6") (pintype "output"))
      (node (ref "E15") (pin "8") (pinfunction "O_8") (pintype "output"))
      (node (ref "E18") (pin "9") (pinfunction "Q_9") (pintype "output"))
      (node (ref "E21") (pin "9") (pinfunction "Q_9") (pintype "output"))
      (node (ref "E3") (pin "8") (pinfunction "O_8") (pintype "output"))
      (node (ref "E6") (pin "8") (pinfunction "O_8") (pintype "output"))
      (node (ref "E9") (pin "5") (pinfunction "I2_5") (pintype "input"))
      (node (ref "U$1") (pin "V2") (pinfunction "1_V2") (pintype "bidirectional"))
    )
    (net (code "37") (name "VCC") (class "Default")
      (node (ref "C1") (pin "1") (pinfunction "1_1") (pintype "passive"))
      (node (ref "C10") (pin "1") (pinfunction "1_1") (pintype "passive"))
      (node (ref "C11") (pin "1") (pinfunction "1_1") (pintype "passive"))
      (node (ref "C12") (pin "1") (pinfunction "1_1") (pintype "passive"))
      (node (ref "C13") (pin "1") (pinfunction "1_1") (pintype "passive"))
      (node (ref "C14") (pin "1") (pinfunction "1_1") (pintype "passive"))
      (node (ref "C15") (pin "1") (pinfunction "1_1") (pintype "passive"))
      (node (ref "C16") (pin "1") (pinfunction "1_1") (pintype "passive"))
      (node (ref "C17") (pin "1") (pinfunction "1_1") (pintype "passive"))
      (node (ref "C18") (pin "1") (pinfunction "1_1") (pintype "passive"))
      (node (ref "C19") (pin "1") (pinfunction "1_1") (pintype "passive"))
      (node (ref "C2") (pin "1") (pinfunction "1_1") (pintype "passive"))
      (node (ref "C20") (pin "1") (pinfunction "1_1") (pintype "passive"))
      (node (ref "C21") (pin "1") (pinfunction "1_1") (pintype "passive"))
      (node (ref "C3") (pin "1") (pinfunction "1_1") (pintype "passive"))
      (node (ref "C4") (pin "1") (pinfunction "1_1") (pintype "passive"))
      (node (ref "C5") (pin "1") (pinfunction "1_1") (pintype "passive"))
      (node (ref "C6") (pin "1") (pinfunction "1_1") (pintype "passive"))
      (node (ref "C7") (pin "1") (pinfunction "1_1") (pintype "passive"))
      (node (ref "C8") (pin "1") (pinfunction "1_1") (pintype "passive"))
      (node (ref "C9") (pin "1") (pinfunction "1_1") (pintype "passive"))
      (node (ref "R2") (pin "2") (pinfunction "2_2") (pintype "passive"))
      (node (ref "R4") (pin "2") (pinfunction "2_2") (pintype "passive"))
      (node (ref "U$1") (pin "A2") (pinfunction "1_A2") (pintype "bidirectional"))
    )
  )
)
